# FX-NVBMP_rev_B.net
KiCad netlist of a schematic drawn in EAGLE
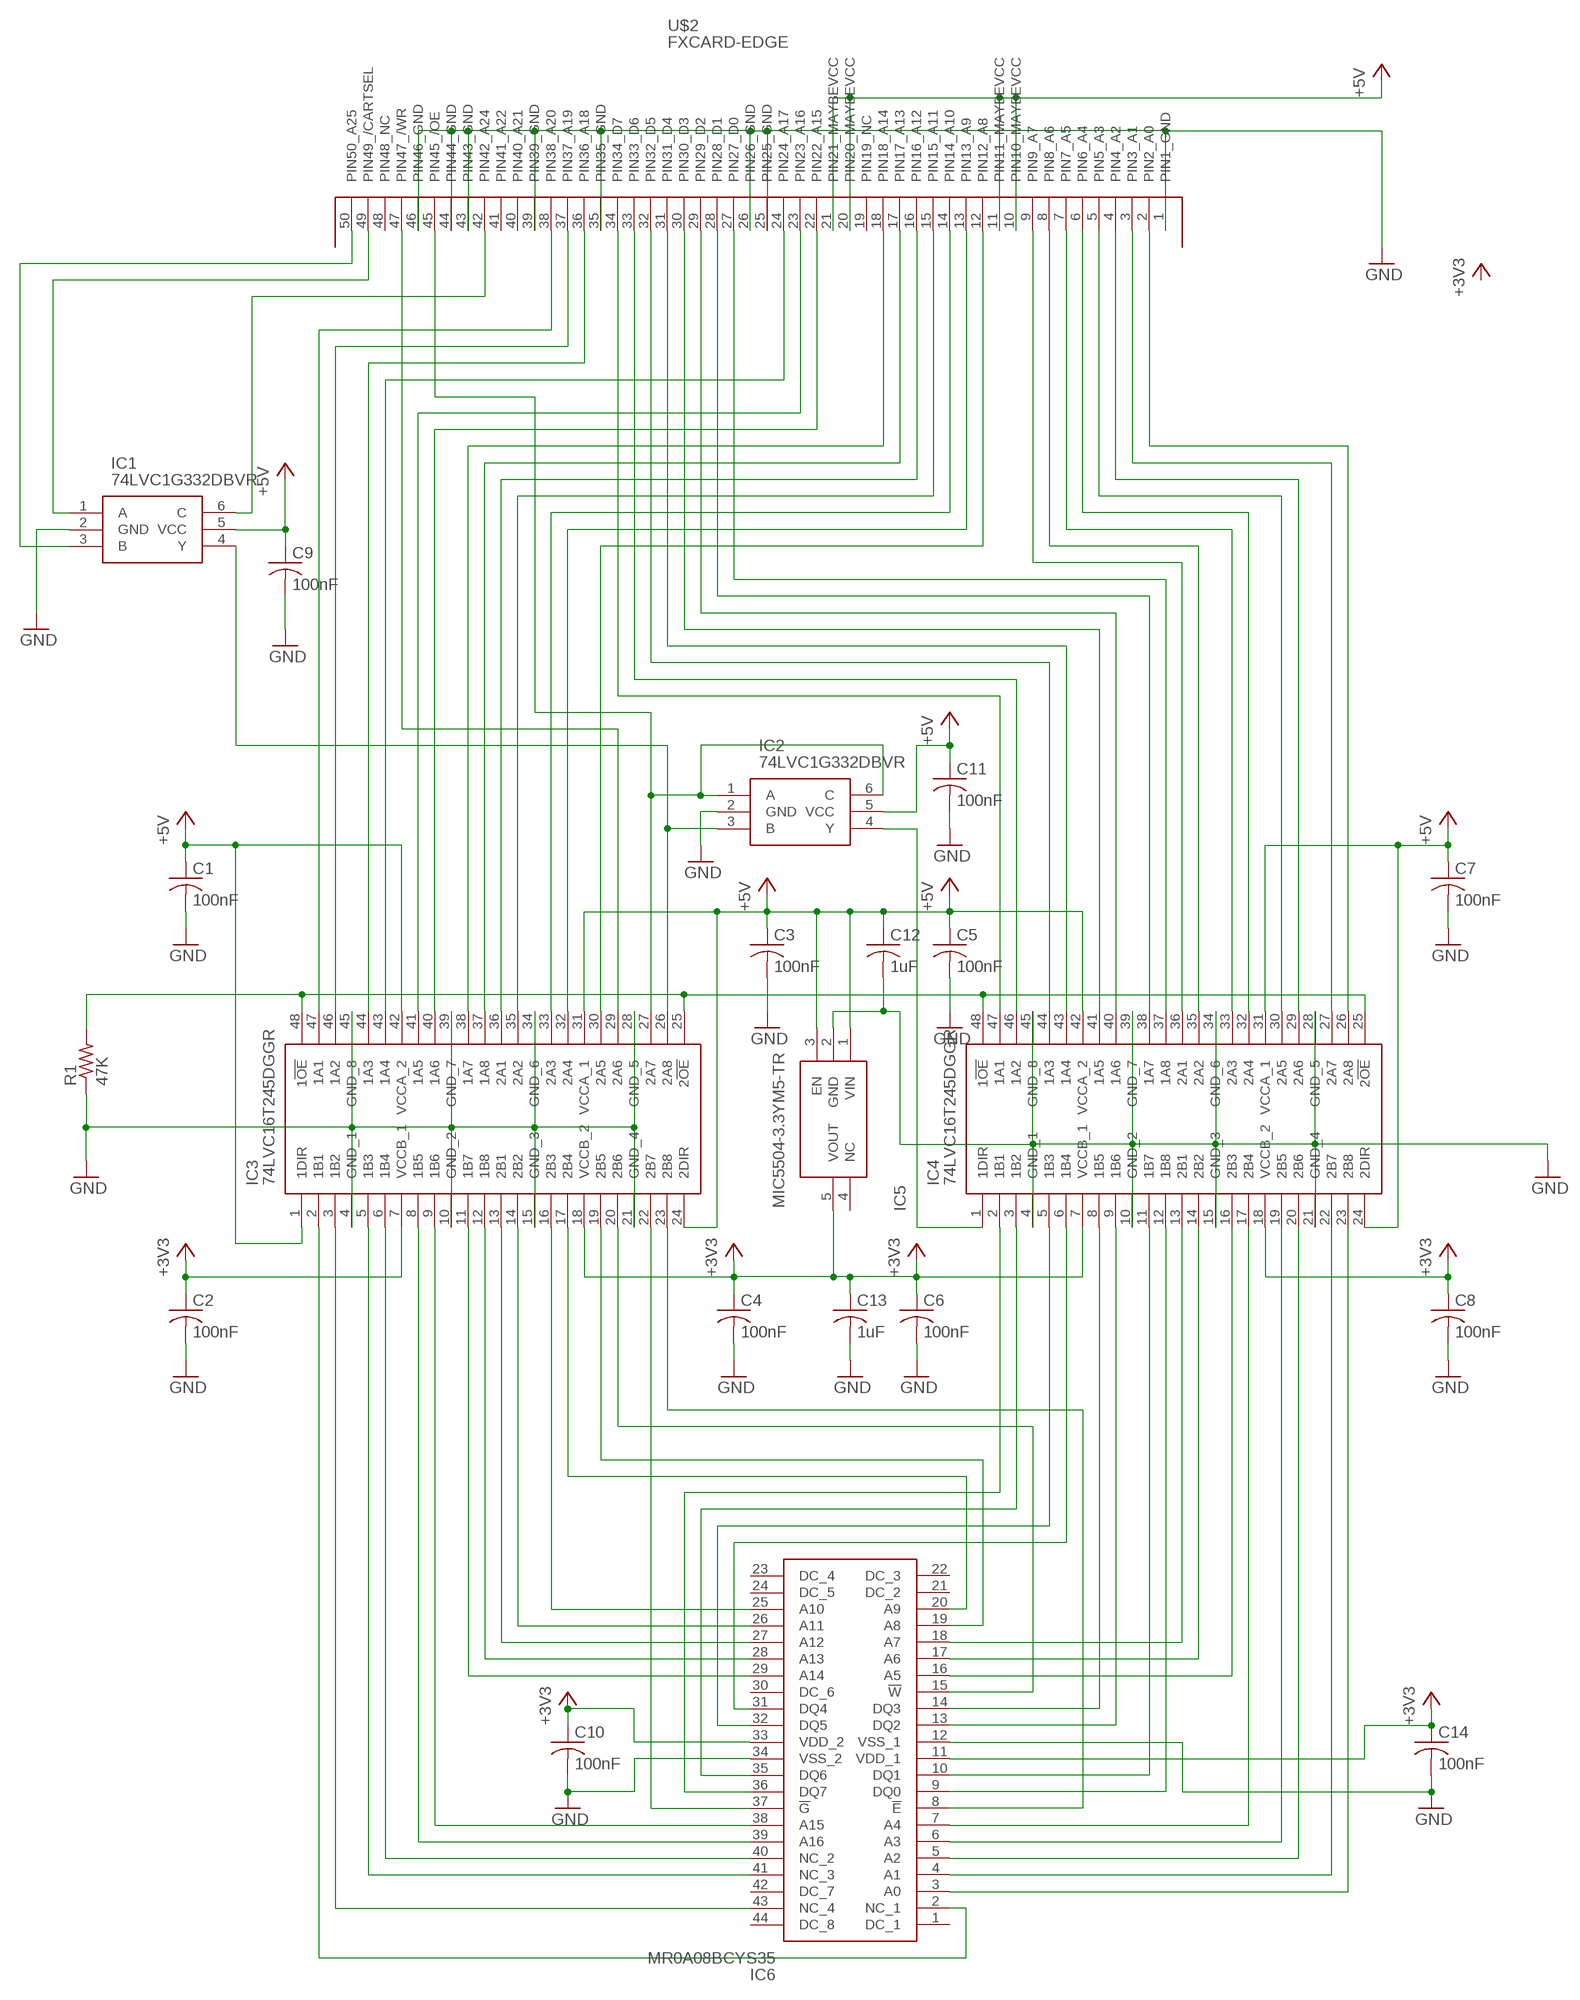
[diagram p0: schematic, sheet 1]

(export (version "E")
  (design (tool "Eeschema 10.0.6"))
  (components
    (comp (ref "C1")
      (value "100nF")
      (footprint "eagle-import:C0402")
      (libsource (lib "eagle-import") (part "C-USC0402"))
    )
    (comp (ref "C2")
      (value "100nF")
      (footprint "eagle-import:C0402")
      (libsource (lib "eagle-import") (part "C-USC0402"))
    )
    (comp (ref "C3")
      (value "100nF")
      (footprint "eagle-import:C0402")
      (libsource (lib "eagle-import") (part "C-USC0402"))
    )
    (comp (ref "C4")
      (value "100nF")
      (footprint "eagle-import:C0402")
      (libsource (lib "eagle-import") (part "C-USC0402"))
    )
    (comp (ref "C5")
      (value "100nF")
      (footprint "eagle-import:C0402")
      (libsource (lib "eagle-import") (part "C-USC0402"))
    )
    (comp (ref "C6")
      (value "100nF")
      (footprint "eagle-import:C0402")
      (libsource (lib "eagle-import") (part "C-USC0402"))
    )
    (comp (ref "C7")
      (value "100nF")
      (footprint "eagle-import:C0402")
      (libsource (lib "eagle-import") (part "C-USC0402"))
    )
    (comp (ref "C8")
      (value "100nF")
      (footprint "eagle-import:C0402")
      (libsource (lib "eagle-import") (part "C-USC0402"))
    )
    (comp (ref "C9")
      (value "100nF")
      (footprint "eagle-import:C0402")
      (libsource (lib "eagle-import") (part "C-USC0402"))
    )
    (comp (ref "C10")
      (value "100nF")
      (footprint "eagle-import:C0402")
      (libsource (lib "eagle-import") (part "C-USC0402"))
    )
    (comp (ref "C11")
      (value "100nF")
      (footprint "eagle-import:C0402")
      (libsource (lib "eagle-import") (part "C-USC0402"))
    )
    (comp (ref "C12")
      (value "1uF")
      (footprint "eagle-import:C0402")
      (libsource (lib "eagle-import") (part "C-USC0402"))
    )
    (comp (ref "C13")
      (value "1uF")
      (footprint "eagle-import:C0402")
      (libsource (lib "eagle-import") (part "C-USC0402"))
    )
    (comp (ref "C14")
      (value "100nF")
      (footprint "eagle-import:C0402")
      (libsource (lib "eagle-import") (part "C-USC0402"))
    )
    (comp (ref "IC1")
      (value "74LVC1G332DBVR")
      (footprint "eagle-import:SOT95P280X145-6N")
      (libsource (lib "eagle-import") (part "74LVC1G332DBVR"))
    )
    (comp (ref "IC2")
      (value "74LVC1G332DBVR")
      (footprint "eagle-import:SOT95P280X145-6N")
      (libsource (lib "eagle-import") (part "74LVC1G332DBVR"))
    )
    (comp (ref "IC3")
      (value "74LVC16T245DGGR")
      (footprint "eagle-import:SOP50P810X120-48N")
      (libsource (lib "eagle-import") (part "74LVC16T245DGGR"))
    )
    (comp (ref "IC4")
      (value "74LVC16T245DGGR")
      (footprint "eagle-import:SOP50P810X120-48N")
      (libsource (lib "eagle-import") (part "74LVC16T245DGGR"))
    )
    (comp (ref "IC5")
      (value "MIC5504-3.3YM5-TR")
      (footprint "eagle-import:SOT95P280X145-5N")
      (fields (field (name "MOUSER_PART_NUMBER") "998-MIC5504-3.3YM5TR"))
      (libsource (lib "eagle-import") (part "MIC5504-3.3YM5-TR"))
    )
    (comp (ref "IC6")
      (value "MR0A08BCYS35")
      (footprint "eagle-import:SOP80P1176X120-44N")
      (libsource (lib "eagle-import") (part "MR0A08BCYS35"))
    )
    (comp (ref "R1")
      (value "47K")
      (footprint "eagle-import:R0402")
      (libsource (lib "eagle-import") (part "R-US_R0402"))
    )
    (comp (ref "U$2")
      (value "FXCARD-EDGE")
      (footprint "eagle-import:FXCARD-EDGE")
      (libsource (lib "eagle-import") (part "FXCARD-EDGE"))
    )
  )
  (nets
    (net (code "1") (name "+3V3") (class "Default")
      (node (ref "C10") (pin "1") (pinfunction "1_1") (pintype "passive"))
      (node (ref "C13") (pin "1") (pinfunction "1_1") (pintype "passive"))
      (node (ref "C14") (pin "1") (pinfunction "1_1") (pintype "passive"))
      (node (ref "C2") (pin "1") (pinfunction "1_1") (pintype "passive"))
      (node (ref "C4") (pin "1") (pinfunction "1_1") (pintype "passive"))
      (node (ref "C6") (pin "1") (pinfunction "1_1") (pintype "passive"))
      (node (ref "C8") (pin "1") (pinfunction "1_1") (pintype "passive"))
      (node (ref "IC3") (pin "18") (pinfunction "VCCB_2_18") (pintype "bidirectional"))
      (node (ref "IC3") (pin "7") (pinfunction "VCCB_1_7") (pintype "bidirectional"))
      (node (ref "IC4") (pin "18") (pinfunction "VCCB_2_18") (pintype "bidirectional"))
      (node (ref "IC4") (pin "7") (pinfunction "VCCB_1_7") (pintype "bidirectional"))
      (node (ref "IC5") (pin "5") (pinfunction "VOUT_5") (pintype "bidirectional"))
      (node (ref "IC6") (pin "11") (pinfunction "VDD_1_11") (pintype "bidirectional"))
      (node (ref "IC6") (pin "33") (pinfunction "VDD_2_33") (pintype "bidirectional"))
    )
    (net (code "2") (name "+5V") (class "Default")
      (node (ref "C1") (pin "1") (pinfunction "1_1") (pintype "passive"))
      (node (ref "C11") (pin "1") (pinfunction "1_1") (pintype "passive"))
      (node (ref "C12") (pin "1") (pinfunction "1_1") (pintype "passive"))
      (node (ref "C3") (pin "1") (pinfunction "1_1") (pintype "passive"))
      (node (ref "C5") (pin "1") (pinfunction "1_1") (pintype "passive"))
      (node (ref "C7") (pin "1") (pinfunction "1_1") (pintype "passive"))
      (node (ref "C9") (pin "1") (pinfunction "1_1") (pintype "passive"))
      (node (ref "IC1") (pin "5") (pinfunction "VCC_5") (pintype "bidirectional"))
      (node (ref "IC2") (pin "5") (pinfunction "VCC_5") (pintype "bidirectional"))
      (node (ref "IC3") (pin "1") (pinfunction "1DIR_1") (pintype "bidirectional"))
      (node (ref "IC3") (pin "24") (pinfunction "2DIR_24") (pintype "bidirectional"))
      (node (ref "IC3") (pin "31") (pinfunction "VCCA_1_31") (pintype "bidirectional"))
      (node (ref "IC3") (pin "42") (pinfunction "VCCA_2_42") (pintype "bidirectional"))
      (node (ref "IC4") (pin "24") (pinfunction "2DIR_24") (pintype "bidirectional"))
      (node (ref "IC4") (pin "31") (pinfunction "VCCA_1_31") (pintype "bidirectional"))
      (node (ref "IC4") (pin "42") (pinfunction "VCCA_2_42") (pintype "bidirectional"))
      (node (ref "IC5") (pin "1") (pinfunction "VIN_1") (pintype "bidirectional"))
      (node (ref "IC5") (pin "3") (pinfunction "EN_3") (pintype "bidirectional"))
      (node (ref "U$2") (pin "10") (pinfunction "PIN10_MAYBEVCC_10") (pintype "bidirectional"))
      (node (ref "U$2") (pin "11") (pinfunction "PIN11_MAYBEVCC_11") (pintype "bidirectional"))
      (node (ref "U$2") (pin "20") (pinfunction "PIN20_MAYBEVCC_20") (pintype "bidirectional"))
      (node (ref "U$2") (pin "21") (pinfunction "PIN21_MAYBEVCC_21") (pintype "bidirectional"))
    )
    (net (code "3") (name "GND") (class "Default")
      (node (ref "C1") (pin "2") (pinfunction "2_2") (pintype "passive"))
      (node (ref "C10") (pin "2") (pinfunction "2_2") (pintype "passive"))
      (node (ref "C11") (pin "2") (pinfunction "2_2") (pintype "passive"))
      (node (ref "C12") (pin "2") (pinfunction "2_2") (pintype "passive"))
      (node (ref "C13") (pin "2") (pinfunction "2_2") (pintype "passive"))
      (node (ref "C14") (pin "2") (pinfunction "2_2") (pintype "passive"))
      (node (ref "C2") (pin "2") (pinfunction "2_2") (pintype "passive"))
      (node (ref "C3") (pin "2") (pinfunction "2_2") (pintype "passive"))
      (node (ref "C4") (pin "2") (pinfunction "2_2") (pintype "passive"))
      (node (ref "C5") (pin "2") (pinfunction "2_2") (pintype "passive"))
      (node (ref "C6") (pin "2") (pinfunction "2_2") (pintype "passive"))
      (node (ref "C7") (pin "2") (pinfunction "2_2") (pintype "passive"))
      (node (ref "C8") (pin "2") (pinfunction "2_2") (pintype "passive"))
      (node (ref "C9") (pin "2") (pinfunction "2_2") (pintype "passive"))
      (node (ref "IC1") (pin "2") (pinfunction "GND_2") (pintype "bidirectional"))
      (node (ref "IC2") (pin "2") (pinfunction "GND_2") (pintype "bidirectional"))
      (node (ref "IC3") (pin "10") (pinfunction "GND_2_10") (pintype "bidirectional"))
      (node (ref "IC3") (pin "15") (pinfunction "GND_3_15") (pintype "bidirectional"))
      (node (ref "IC3") (pin "21") (pinfunction "GND_4_21") (pintype "bidirectional"))
      (node (ref "IC3") (pin "28") (pinfunction "GND_5_28") (pintype "bidirectional"))
      (node (ref "IC3") (pin "34") (pinfunction "GND_6_34") (pintype "bidirectional"))
      (node (ref "IC3") (pin "39") (pinfunction "GND_7_39") (pintype "bidirectional"))
      (node (ref "IC3") (pin "4") (pinfunction "GND_1_4") (pintype "bidirectional"))
      (node (ref "IC3") (pin "45") (pinfunction "GND_8_45") (pintype "bidirectional"))
      (node (ref "IC4") (pin "10") (pinfunction "GND_2_10") (pintype "bidirectional"))
      (node (ref "IC4") (pin "15") (pinfunction "GND_3_15") (pintype "bidirectional"))
      (node (ref "IC4") (pin "21") (pinfunction "GND_4_21") (pintype "bidirectional"))
      (node (ref "IC4") (pin "28") (pinfunction "GND_5_28") (pintype "bidirectional"))
      (node (ref "IC4") (pin "34") (pinfunction "GND_6_34") (pintype "bidirectional"))
      (node (ref "IC4") (pin "39") (pinfunction "GND_7_39") (pintype "bidirectional"))
      (node (ref "IC4") (pin "4") (pinfunction "GND_1_4") (pintype "bidirectional"))
      (node (ref "IC4") (pin "45") (pinfunction "GND_8_45") (pintype "bidirectional"))
      (node (ref "IC5") (pin "2") (pinfunction "GND_2") (pintype "bidirectional"))
      (node (ref "IC6") (pin "12") (pinfunction "VSS_1_12") (pintype "bidirectional"))
      (node (ref "IC6") (pin "34") (pinfunction "VSS_2_34") (pintype "bidirectional"))
      (node (ref "R1") (pin "1") (pinfunction "1_1") (pintype "passive"))
      (node (ref "U$2") (pin "1") (pinfunction "PIN1_GND_1") (pintype "power_in"))
      (node (ref "U$2") (pin "25") (pinfunction "PIN25_GND_25") (pintype "power_in"))
      (node (ref "U$2") (pin "26") (pinfunction "PIN26_GND_26") (pintype "power_in"))
      (node (ref "U$2") (pin "35") (pinfunction "PIN35_GND_35") (pintype "power_in"))
      (node (ref "U$2") (pin "39") (pinfunction "PIN39_GND_39") (pintype "power_in"))
      (node (ref "U$2") (pin "43") (pinfunction "PIN43_GND_43") (pintype "power_in"))
      (node (ref "U$2") (pin "44") (pinfunction "PIN44_GND_44") (pintype "power_in"))
      (node (ref "U$2") (pin "46") (pinfunction "PIN46_GND_46") (pintype "power_in"))
    )
    (net (code "4") (name "Net-(IC1-A)") (class "Default")
      (node (ref "IC1") (pin "1") (pinfunction "A_1") (pintype "bidirectional"))
      (node (ref "U$2") (pin "49") (pinfunction "PIN49_/CARTSEL_49") (pintype "bidirectional"))
    )
    (net (code "5") (name "Net-(IC1-B)") (class "Default")
      (node (ref "IC1") (pin "3") (pinfunction "B_3") (pintype "bidirectional"))
      (node (ref "U$2") (pin "50") (pinfunction "PIN50_A25_50") (pintype "bidirectional"))
    )
    (net (code "6") (name "Net-(IC1-C)") (class "Default")
      (node (ref "IC1") (pin "6") (pinfunction "C_6") (pintype "bidirectional"))
      (node (ref "U$2") (pin "42") (pinfunction "PIN42_A24_42") (pintype "bidirectional"))
    )
    (net (code "7") (name "Net-(IC1-Y)") (class "Default")
      (node (ref "IC1") (pin "4") (pinfunction "Y_4") (pintype "bidirectional"))
      (node (ref "IC2") (pin "3") (pinfunction "B_3") (pintype "bidirectional"))
      (node (ref "IC3") (pin "26") (pinfunction "2A8_26") (pintype "bidirectional"))
    )
    (net (code "8") (name "Net-(IC2-A)") (class "Default")
      (node (ref "IC2") (pin "1") (pinfunction "A_1") (pintype "bidirectional"))
      (node (ref "IC2") (pin "6") (pinfunction "C_6") (pintype "bidirectional"))
      (node (ref "IC3") (pin "27") (pinfunction "2A7_27") (pintype "bidirectional"))
      (node (ref "U$2") (pin "45") (pinfunction "PIN45_/OE_45") (pintype "bidirectional"))
    )
    (net (code "9") (name "Net-(IC2-Y)") (class "Default")
      (node (ref "IC2") (pin "4") (pinfunction "Y_4") (pintype "bidirectional"))
      (node (ref "IC4") (pin "1") (pinfunction "1DIR_1") (pintype "bidirectional"))
    )
    (net (code "10") (name "Net-(IC3-1A1)") (class "Default")
      (node (ref "IC3") (pin "47") (pinfunction "1A1_47") (pintype "bidirectional"))
      (node (ref "U$2") (pin "38") (pinfunction "PIN38_A20_38") (pintype "bidirectional"))
    )
    (net (code "11") (name "Net-(IC3-1A2)") (class "Default")
      (node (ref "IC3") (pin "46") (pinfunction "1A2_46") (pintype "bidirectional"))
      (node (ref "U$2") (pin "37") (pinfunction "PIN37_A19_37") (pintype "bidirectional"))
    )
    (net (code "12") (name "Net-(IC3-1A3)") (class "Default")
      (node (ref "IC3") (pin "44") (pinfunction "1A3_44") (pintype "bidirectional"))
      (node (ref "U$2") (pin "36") (pinfunction "PIN36_A18_36") (pintype "bidirectional"))
    )
    (net (code "13") (name "Net-(IC3-1A4)") (class "Default")
      (node (ref "IC3") (pin "43") (pinfunction "1A4_43") (pintype "bidirectional"))
      (node (ref "U$2") (pin "24") (pinfunction "PIN24_A17_24") (pintype "bidirectional"))
    )
    (net (code "14") (name "Net-(IC3-1A5)") (class "Default")
      (node (ref "IC3") (pin "41") (pinfunction "1A5_41") (pintype "bidirectional"))
      (node (ref "U$2") (pin "23") (pinfunction "PIN23_A16_23") (pintype "bidirectional"))
    )
    (net (code "15") (name "Net-(IC3-1A6)") (class "Default")
      (node (ref "IC3") (pin "40") (pinfunction "1A6_40") (pintype "bidirectional"))
      (node (ref "U$2") (pin "22") (pinfunction "PIN22_A15_22") (pintype "bidirectional"))
    )
    (net (code "16") (name "Net-(IC3-1A7)") (class "Default")
      (node (ref "IC3") (pin "38") (pinfunction "1A7_38") (pintype "bidirectional"))
      (node (ref "U$2") (pin "18") (pinfunction "PIN18_A14_18") (pintype "bidirectional"))
    )
    (net (code "17") (name "Net-(IC3-1A8)") (class "Default")
      (node (ref "IC3") (pin "37") (pinfunction "1A8_37") (pintype "bidirectional"))
      (node (ref "U$2") (pin "17") (pinfunction "PIN17_A13_17") (pintype "bidirectional"))
    )
    (net (code "18") (name "Net-(IC3-1B1)") (class "Default")
      (node (ref "IC3") (pin "2") (pinfunction "1B1_2") (pintype "bidirectional"))
      (node (ref "IC6") (pin "2") (pinfunction "NC_1_2") (pintype "bidirectional"))
    )
    (net (code "19") (name "Net-(IC3-1B2)") (class "Default")
      (node (ref "IC3") (pin "3") (pinfunction "1B2_3") (pintype "bidirectional"))
      (node (ref "IC6") (pin "43") (pinfunction "NC_4_43") (pintype "bidirectional"))
    )
    (net (code "20") (name "Net-(IC3-1B3)") (class "Default")
      (node (ref "IC3") (pin "5") (pinfunction "1B3_5") (pintype "bidirectional"))
      (node (ref "IC6") (pin "41") (pinfunction "NC_3_41") (pintype "bidirectional"))
    )
    (net (code "21") (name "Net-(IC3-1B4)") (class "Default")
      (node (ref "IC3") (pin "6") (pinfunction "1B4_6") (pintype "bidirectional"))
      (node (ref "IC6") (pin "40") (pinfunction "NC_2_40") (pintype "bidirectional"))
    )
    (net (code "22") (name "Net-(IC3-1B5)") (class "Default")
      (node (ref "IC3") (pin "8") (pinfunction "1B5_8") (pintype "bidirectional"))
      (node (ref "IC6") (pin "39") (pinfunction "A16_39") (pintype "bidirectional"))
    )
    (net (code "23") (name "Net-(IC3-1B6)") (class "Default")
      (node (ref "IC3") (pin "9") (pinfunction "1B6_9") (pintype "bidirectional"))
      (node (ref "IC6") (pin "38") (pinfunction "A15_38") (pintype "bidirectional"))
    )
    (net (code "24") (name "Net-(IC3-1B7)") (class "Default")
      (node (ref "IC3") (pin "11") (pinfunction "1B7_11") (pintype "bidirectional"))
      (node (ref "IC6") (pin "29") (pinfunction "A14_29") (pintype "bidirectional"))
    )
    (net (code "25") (name "Net-(IC3-1B8)") (class "Default")
      (node (ref "IC3") (pin "12") (pinfunction "1B8_12") (pintype "bidirectional"))
      (node (ref "IC6") (pin "28") (pinfunction "A13_28") (pintype "bidirectional"))
    )
    (net (code "26") (name "Net-(IC3-1~{OE})") (class "Default")
      (node (ref "IC3") (pin "25") (pinfunction "2~{OE}_25") (pintype "bidirectional"))
      (node (ref "IC3") (pin "48") (pinfunction "1~{OE}_48") (pintype "bidirectional"))
      (node (ref "IC4") (pin "25") (pinfunction "2~{OE}_25") (pintype "bidirectional"))
      (node (ref "IC4") (pin "48") (pinfunction "1~{OE}_48") (pintype "bidirectional"))
      (node (ref "R1") (pin "2") (pinfunction "2_2") (pintype "passive"))
    )
    (net (code "27") (name "Net-(IC3-2A1)") (class "Default")
      (node (ref "IC3") (pin "36") (pinfunction "2A1_36") (pintype "bidirectional"))
      (node (ref "U$2") (pin "16") (pinfunction "PIN16_A12_16") (pintype "bidirectional"))
    )
    (net (code "28") (name "Net-(IC3-2A2)") (class "Default")
      (node (ref "IC3") (pin "35") (pinfunction "2A2_35") (pintype "bidirectional"))
      (node (ref "U$2") (pin "15") (pinfunction "PIN15_A11_15") (pintype "bidirectional"))
    )
    (net (code "29") (name "Net-(IC3-2A3)") (class "Default")
      (node (ref "IC3") (pin "33") (pinfunction "2A3_33") (pintype "bidirectional"))
      (node (ref "U$2") (pin "14") (pinfunction "PIN14_A10_14") (pintype "bidirectional"))
    )
    (net (code "30") (name "Net-(IC3-2A4)") (class "Default")
      (node (ref "IC3") (pin "32") (pinfunction "2A4_32") (pintype "bidirectional"))
      (node (ref "U$2") (pin "13") (pinfunction "PIN13_A9_13") (pintype "bidirectional"))
    )
    (net (code "31") (name "Net-(IC3-2A5)") (class "Default")
      (node (ref "IC3") (pin "30") (pinfunction "2A5_30") (pintype "bidirectional"))
      (node (ref "U$2") (pin "12") (pinfunction "PIN12_A8_12") (pintype "bidirectional"))
    )
    (net (code "32") (name "Net-(IC3-2A6)") (class "Default")
      (node (ref "IC3") (pin "29") (pinfunction "2A6_29") (pintype "bidirectional"))
      (node (ref "U$2") (pin "47") (pinfunction "PIN47_/WR_47") (pintype "bidirectional"))
    )
    (net (code "33") (name "Net-(IC3-2B1)") (class "Default")
      (node (ref "IC3") (pin "13") (pinfunction "2B1_13") (pintype "bidirectional"))
      (node (ref "IC6") (pin "27") (pinfunction "A12_27") (pintype "bidirectional"))
    )
    (net (code "34") (name "Net-(IC3-2B2)") (class "Default")
      (node (ref "IC3") (pin "14") (pinfunction "2B2_14") (pintype "bidirectional"))
      (node (ref "IC6") (pin "26") (pinfunction "A11_26") (pintype "bidirectional"))
    )
    (net (code "35") (name "Net-(IC3-2B3)") (class "Default")
      (node (ref "IC3") (pin "16") (pinfunction "2B3_16") (pintype "bidirectional"))
      (node (ref "IC6") (pin "25") (pinfunction "A10_25") (pintype "bidirectional"))
    )
    (net (code "36") (name "Net-(IC3-2B4)") (class "Default")
      (node (ref "IC3") (pin "17") (pinfunction "2B4_17") (pintype "bidirectional"))
      (node (ref "IC6") (pin "20") (pinfunction "A9_20") (pintype "bidirectional"))
    )
    (net (code "37") (name "Net-(IC3-2B5)") (class "Default")
      (node (ref "IC3") (pin "19") (pinfunction "2B5_19") (pintype "bidirectional"))
      (node (ref "IC6") (pin "19") (pinfunction "A8_19") (pintype "bidirectional"))
    )
    (net (code "38") (name "Net-(IC3-2B6)") (class "Default")
      (node (ref "IC3") (pin "20") (pinfunction "2B6_20") (pintype "bidirectional"))
      (node (ref "IC6") (pin "15") (pinfunction "~{W}_15") (pintype "bidirectional"))
    )
    (net (code "39") (name "Net-(IC3-2B7)") (class "Default")
      (node (ref "IC3") (pin "22") (pinfunction "2B7_22") (pintype "bidirectional"))
      (node (ref "IC6") (pin "37") (pinfunction "~{G}_37") (pintype "bidirectional"))
    )
    (net (code "40") (name "Net-(IC3-2B8)") (class "Default")
      (node (ref "IC3") (pin "23") (pinfunction "2B8_23") (pintype "bidirectional"))
      (node (ref "IC6") (pin "8") (pinfunction "~{E}_8") (pintype "bidirectional"))
    )
    (net (code "41") (name "Net-(IC4-1A1)") (class "Default")
      (node (ref "IC4") (pin "47") (pinfunction "1A1_47") (pintype "bidirectional"))
      (node (ref "U$2") (pin "34") (pinfunction "PIN34_D7_34") (pintype "bidirectional"))
    )
    (net (code "42") (name "Net-(IC4-1A2)") (class "Default")
      (node (ref "IC4") (pin "46") (pinfunction "1A2_46") (pintype "bidirectional"))
      (node (ref "U$2") (pin "33") (pinfunction "PIN33_D6_33") (pintype "bidirectional"))
    )
    (net (code "43") (name "Net-(IC4-1A3)") (class "Default")
      (node (ref "IC4") (pin "44") (pinfunction "1A3_44") (pintype "bidirectional"))
      (node (ref "U$2") (pin "32") (pinfunction "PIN32_D5_32") (pintype "bidirectional"))
    )
    (net (code "44") (name "Net-(IC4-1A4)") (class "Default")
      (node (ref "IC4") (pin "43") (pinfunction "1A4_43") (pintype "bidirectional"))
      (node (ref "U$2") (pin "31") (pinfunction "PIN31_D4_31") (pintype "bidirectional"))
    )
    (net (code "45") (name "Net-(IC4-1A5)") (class "Default")
      (node (ref "IC4") (pin "41") (pinfunction "1A5_41") (pintype "bidirectional"))
      (node (ref "U$2") (pin "30") (pinfunction "PIN30_D3_30") (pintype "bidirectional"))
    )
    (net (code "46") (name "Net-(IC4-1A6)") (class "Default")
      (node (ref "IC4") (pin "40") (pinfunction "1A6_40") (pintype "bidirectional"))
      (node (ref "U$2") (pin "29") (pinfunction "PIN29_D2_29") (pintype "bidirectional"))
    )
    (net (code "47") (name "Net-(IC4-1A7)") (class "Default")
      (node (ref "IC4") (pin "38") (pinfunction "1A7_38") (pintype "bidirectional"))
      (node (ref "U$2") (pin "28") (pinfunction "PIN28_D1_28") (pintype "bidirectional"))
    )
    (net (code "48") (name "Net-(IC4-1A8)") (class "Default")
      (node (ref "IC4") (pin "37") (pinfunction "1A8_37") (pintype "bidirectional"))
      (node (ref "U$2") (pin "27") (pinfunction "PIN27_D0_27") (pintype "bidirectional"))
    )
    (net (code "49") (name "Net-(IC4-1B1)") (class "Default")
      (node (ref "IC4") (pin "2") (pinfunction "1B1_2") (pintype "bidirectional"))
      (node (ref "IC6") (pin "36") (pinfunction "DQ7_36") (pintype "bidirectional"))
    )
    (net (code "50") (name "Net-(IC4-1B2)") (class "Default")
      (node (ref "IC4") (pin "3") (pinfunction "1B2_3") (pintype "bidirectional"))
      (node (ref "IC6") (pin "35") (pinfunction "DQ6_35") (pintype "bidirectional"))
    )
    (net (code "51") (name "Net-(IC4-1B3)") (class "Default")
      (node (ref "IC4") (pin "5") (pinfunction "1B3_5") (pintype "bidirectional"))
      (node (ref "IC6") (pin "32") (pinfunction "DQ5_32") (pintype "bidirectional"))
    )
    (net (code "52") (name "Net-(IC4-1B4)") (class "Default")
      (node (ref "IC4") (pin "6") (pinfunction "1B4_6") (pintype "bidirectional"))
      (node (ref "IC6") (pin "31") (pinfunction "DQ4_31") (pintype "bidirectional"))
    )
    (net (code "53") (name "Net-(IC4-1B5)") (class "Default")
      (node (ref "IC4") (pin "8") (pinfunction "1B5_8") (pintype "bidirectional"))
      (node (ref "IC6") (pin "14") (pinfunction "DQ3_14") (pintype "bidirectional"))
    )
    (net (code "54") (name "Net-(IC4-1B6)") (class "Default")
      (node (ref "IC4") (pin "9") (pinfunction "1B6_9") (pintype "bidirectional"))
      (node (ref "IC6") (pin "13") (pinfunction "DQ2_13") (pintype "bidirectional"))
    )
    (net (code "55") (name "Net-(IC4-1B7)") (class "Default")
      (node (ref "IC4") (pin "11") (pinfunction "1B7_11") (pintype "bidirectional"))
      (node (ref "IC6") (pin "10") (pinfunction "DQ1_10") (pintype "bidirectional"))
    )
    (net (code "56") (name "Net-(IC4-1B8)") (class "Default")
      (node (ref "IC4") (pin "12") (pinfunction "1B8_12") (pintype "bidirectional"))
      (node (ref "IC6") (pin "9") (pinfunction "DQ0_9") (pintype "bidirectional"))
    )
    (net (code "57") (name "Net-(IC4-2A1)") (class "Default")
      (node (ref "IC4") (pin "36") (pinfunction "2A1_36") (pintype "bidirectional"))
      (node (ref "U$2") (pin "9") (pinfunction "PIN9_A7_9") (pintype "bidirectional"))
    )
    (net (code "58") (name "Net-(IC4-2A2)") (class "Default")
      (node (ref "IC4") (pin "35") (pinfunction "2A2_35") (pintype "bidirectional"))
      (node (ref "U$2") (pin "8") (pinfunction "PIN8_A6_8") (pintype "bidirectional"))
    )
    (net (code "59") (name "Net-(IC4-2A3)") (class "Default")
      (node (ref "IC4") (pin "33") (pinfunction "2A3_33") (pintype "bidirectional"))
      (node (ref "U$2") (pin "7") (pinfunction "PIN7_A5_7") (pintype "bidirectional"))
    )
    (net (code "60") (name "Net-(IC4-2A4)") (class "Default")
      (node (ref "IC4") (pin "32") (pinfunction "2A4_32") (pintype "bidirectional"))
      (node (ref "U$2") (pin "6") (pinfunction "PIN6_A4_6") (pintype "bidirectional"))
    )
    (net (code "61") (name "Net-(IC4-2A5)") (class "Default")
      (node (ref "IC4") (pin "30") (pinfunction "2A5_30") (pintype "bidirectional"))
      (node (ref "U$2") (pin "5") (pinfunction "PIN5_A3_5") (pintype "bidirectional"))
    )
    (net (code "62") (name "Net-(IC4-2A6)") (class "Default")
      (node (ref "IC4") (pin "29") (pinfunction "2A6_29") (pintype "bidirectional"))
      (node (ref "U$2") (pin "4") (pinfunction "PIN4_A2_4") (pintype "bidirectional"))
    )
    (net (code "63") (name "Net-(IC4-2A7)") (class "Default")
      (node (ref "IC4") (pin "27") (pinfunction "2A7_27") (pintype "bidirectional"))
      (node (ref "U$2") (pin "3") (pinfunction "PIN3_A1_3") (pintype "bidirectional"))
    )
    (net (code "64") (name "Net-(IC4-2A8)") (class "Default")
      (node (ref "IC4") (pin "26") (pinfunction "2A8_26") (pintype "bidirectional"))
      (node (ref "U$2") (pin "2") (pinfunction "PIN2_A0_2") (pintype "bidirectional"))
    )
    (net (code "65") (name "Net-(IC4-2B1)") (class "Default")
      (node (ref "IC4") (pin "13") (pinfunction "2B1_13") (pintype "bidirectional"))
      (node (ref "IC6") (pin "18") (pinfunction "A7_18") (pintype "bidirectional"))
    )
    (net (code "66") (name "Net-(IC4-2B2)") (class "Default")
      (node (ref "IC4") (pin "14") (pinfunction "2B2_14") (pintype "bidirectional"))
      (node (ref "IC6") (pin "17") (pinfunction "A6_17") (pintype "bidirectional"))
    )
    (net (code "67") (name "Net-(IC4-2B3)") (class "Default")
      (node (ref "IC4") (pin "16") (pinfunction "2B3_16") (pintype "bidirectional"))
      (node (ref "IC6") (pin "16") (pinfunction "A5_16") (pintype "bidirectional"))
    )
    (net (code "68") (name "Net-(IC4-2B4)") (class "Default")
      (node (ref "IC4") (pin "17") (pinfunction "2B4_17") (pintype "bidirectional"))
      (node (ref "IC6") (pin "7") (pinfunction "A4_7") (pintype "bidirectional"))
    )
    (net (code "69") (name "Net-(IC4-2B5)") (class "Default")
      (node (ref "IC4") (pin "19") (pinfunction "2B5_19") (pintype "bidirectional"))
      (node (ref "IC6") (pin "6") (pinfunction "A3_6") (pintype "bidirectional"))
    )
    (net (code "70") (name "Net-(IC4-2B6)") (class "Default")
      (node (ref "IC4") (pin "20") (pinfunction "2B6_20") (pintype "bidirectional"))
      (node (ref "IC6") (pin "5") (pinfunction "A2_5") (pintype "bidirectional"))
    )
    (net (code "71") (name "Net-(IC4-2B7)") (class "Default")
      (node (ref "IC4") (pin "22") (pinfunction "2B7_22") (pintype "bidirectional"))
      (node (ref "IC6") (pin "4") (pinfunction "A1_4") (pintype "bidirectional"))
    )
    (net (code "72") (name "Net-(IC4-2B8)") (class "Default")
      (node (ref "IC4") (pin "23") (pinfunction "2B8_23") (pintype "bidirectional"))
      (node (ref "IC6") (pin "3") (pinfunction "A0_3") (pintype "bidirectional"))
    )
    (net (code "73") (name "unconnected-(IC5-NC-Pad4)") (class "Default")
      (node (ref "IC5") (pin "4") (pinfunction "NC_4") (pintype "no_connect"))
    )
    (net (code "74") (name "unconnected-(IC6-DC_1-Pad1)") (class "Default")
      (node (ref "IC6") (pin "1") (pinfunction "DC_1_1") (pintype "bidirectional"))
    )
    (net (code "75") (name "unconnected-(IC6-DC_2-Pad21)") (class "Default")
      (node (ref "IC6") (pin "21") (pinfunction "DC_2_21") (pintype "bidirectional"))
    )
    (net (code "76") (name "unconnected-(IC6-DC_3-Pad22)") (class "Default")
      (node (ref "IC6") (pin "22") (pinfunction "DC_3_22") (pintype "bidirectional"))
    )
    (net (code "77") (name "unconnected-(IC6-DC_4-Pad23)") (class "Default")
      (node (ref "IC6") (pin "23") (pinfunction "DC_4_23") (pintype "bidirectional"))
    )
    (net (code "78") (name "unconnected-(IC6-DC_5-Pad24)") (class "Default")
      (node (ref "IC6") (pin "24") (pinfunction "DC_5_24") (pintype "bidirectional"))
    )
    (net (code "79") (name "unconnected-(IC6-DC_6-Pad30)") (class "Default")
      (node (ref "IC6") (pin "30") (pinfunction "DC_6_30") (pintype "bidirectional"))
    )
    (net (code "80") (name "unconnected-(IC6-DC_7-Pad42)") (class "Default")
      (node (ref "IC6") (pin "42") (pinfunction "DC_7_42") (pintype "bidirectional"))
    )
    (net (code "81") (name "unconnected-(IC6-DC_8-Pad44)") (class "Default")
      (node (ref "IC6") (pin "44") (pinfunction "DC_8_44") (pintype "bidirectional"))
    )
    (net (code "82") (name "unconnected-(U$2-PIN19_NC-Pad19)") (class "Default")
      (node (ref "U$2") (pin "19") (pinfunction "PIN19_NC_19") (pintype "bidirectional"))
    )
    (net (code "83") (name "unconnected-(U$2-PIN40_A21-Pad40)") (class "Default")
      (node (ref "U$2") (pin "40") (pinfunction "PIN40_A21_40") (pintype "bidirectional"))
    )
    (net (code "84") (name "unconnected-(U$2-PIN41_A22-Pad41)") (class "Default")
      (node (ref "U$2") (pin "41") (pinfunction "PIN41_A22_41") (pintype "bidirectional"))
    )
    (net (code "85") (name "unconnected-(U$2-PIN48_NC-Pad48)") (class "Default")
      (node (ref "U$2") (pin "48") (pinfunction "PIN48_NC_48") (pintype "bidirectional"))
    )
  )
)
